# dual_power_supply.net
KiCad netlist of a schematic drawn in EAGLE
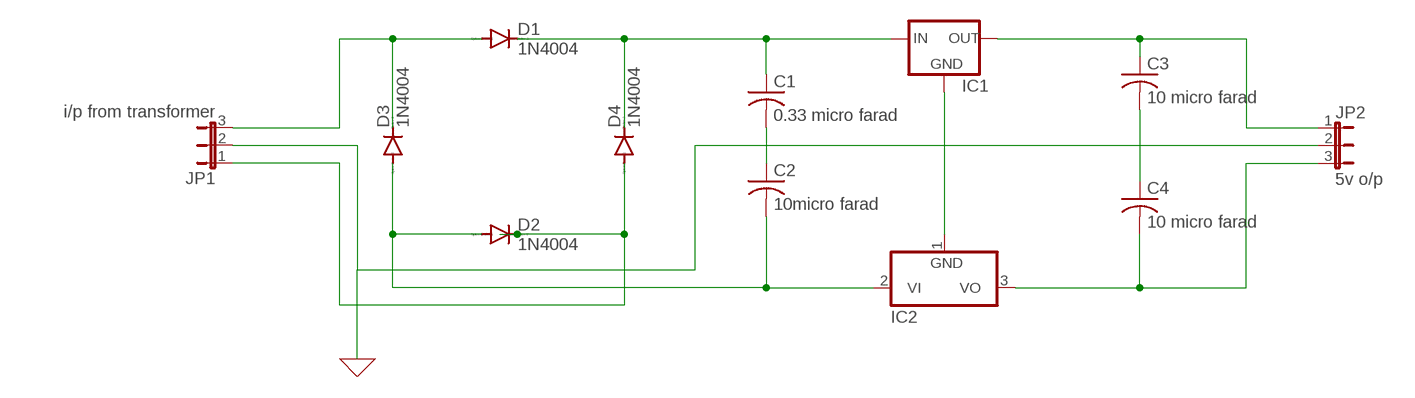
[diagram p0: schematic, sheet 1]

(export (version "E")
  (design (tool "Eeschema 10.0.6"))
  (components
    (comp (ref "C1")
      (value "0.33 micro farad")
      (footprint "eagle-import:C025-025X050")
      (libsource (lib "eagle-import") (part "C-US025-025X050"))
    )
    (comp (ref "C2")
      (value "10micro farad")
      (footprint "eagle-import:C025-025X050")
      (libsource (lib "eagle-import") (part "C-US025-025X050"))
    )
    (comp (ref "C3")
      (value "10 micro farad")
      (footprint "eagle-import:C025-025X050")
      (libsource (lib "eagle-import") (part "C-US025-025X050"))
    )
    (comp (ref "C4")
      (value "10 micro farad")
      (footprint "eagle-import:C025-025X050")
      (libsource (lib "eagle-import") (part "C-US025-025X050"))
    )
    (comp (ref "D1")
      (value "1N4004")
      (footprint "eagle-import:DO41-10")
      (libsource (lib "eagle-import") (part "1N4004"))
    )
    (comp (ref "D2")
      (value "1N4004")
      (footprint "eagle-import:DO41-10")
      (libsource (lib "eagle-import") (part "1N4004"))
    )
    (comp (ref "D3")
      (value "1N4004")
      (footprint "eagle-import:DO41-10")
      (libsource (lib "eagle-import") (part "1N4004"))
    )
    (comp (ref "D4")
      (value "1N4004")
      (footprint "eagle-import:DO41-10")
      (libsource (lib "eagle-import") (part "1N4004"))
    )
    (comp (ref "IC1")
      (value "78MXXS")
      (footprint "eagle-import:78MXXS")
      (libsource (lib "eagle-import") (part "78MXXS"))
    )
    (comp (ref "IC2")
      (value "7905L")
      (footprint "eagle-import:TO92")
      (libsource (lib "eagle-import") (part "79L05"))
    )
    (comp (ref "JP1")
      (value "i/p from transformer")
      (footprint "eagle-import:JP2")
      (libsource (lib "eagle-import") (part "JP2E"))
    )
    (comp (ref "JP2")
      (value "5v o/p")
      (footprint "eagle-import:JP2")
      (libsource (lib "eagle-import") (part "JP2E"))
    )
  )
  (nets
    (net (code "1") (name "GND") (class "Default")
      (node (ref "JP1") (pin "2") (pinfunction "2_2") (pintype "passive"))
      (node (ref "JP2") (pin "2") (pinfunction "2_2") (pintype "passive"))
    )
    (net (code "2") (name "Net-(C1-Pad1)") (class "Default")
      (node (ref "C1") (pin "1") (pinfunction "1_1") (pintype "passive"))
      (node (ref "D1") (pin "C") (pinfunction "C_C") (pintype "passive"))
      (node (ref "D4") (pin "C") (pinfunction "C_C") (pintype "passive"))
      (node (ref "IC1") (pin "IN") (pinfunction "IN_IN") (pintype "input"))
    )
    (net (code "3") (name "Net-(C1-Pad2)") (class "Default")
      (node (ref "C1") (pin "2") (pinfunction "2_2") (pintype "passive"))
      (node (ref "C2") (pin "1") (pinfunction "1_1") (pintype "passive"))
    )
    (net (code "4") (name "Net-(C3-Pad1)") (class "Default")
      (node (ref "C3") (pin "1") (pinfunction "1_1") (pintype "passive"))
      (node (ref "IC1") (pin "OUT") (pinfunction "OUT_OUT") (pintype "passive"))
      (node (ref "JP2") (pin "1") (pinfunction "1_1") (pintype "passive"))
    )
    (net (code "5") (name "Net-(C3-Pad2)") (class "Default")
      (node (ref "C3") (pin "2") (pinfunction "2_2") (pintype "passive"))
      (node (ref "C4") (pin "1") (pinfunction "1_1") (pintype "passive"))
    )
    (net (code "6") (name "Net-(D1-PadA)") (class "Default")
      (node (ref "D1") (pin "A") (pinfunction "A_A") (pintype "passive"))
      (node (ref "D3") (pin "C") (pinfunction "C_C") (pintype "passive"))
      (node (ref "JP1") (pin "3") (pinfunction "3_3") (pintype "passive"))
    )
    (net (code "7") (name "Net-(D2-PadC)") (class "Default")
      (node (ref "D2") (pin "C") (pinfunction "C_C") (pintype "passive"))
      (node (ref "D4") (pin "A") (pinfunction "A_A") (pintype "passive"))
      (node (ref "JP1") (pin "1") (pinfunction "1_1") (pintype "passive"))
    )
    (net (code "8") (name "Net-(IC2-GND)") (class "Default")
      (node (ref "IC1") (pin "GND") (pinfunction "GND_GND") (pintype "input"))
      (node (ref "IC2") (pin "1") (pinfunction "GND_1") (pintype "passive"))
    )
    (net (code "9") (name "Net-(IC2-VI)") (class "Default")
      (node (ref "C2") (pin "2") (pinfunction "2_2") (pintype "passive"))
      (node (ref "D2") (pin "A") (pinfunction "A_A") (pintype "passive"))
      (node (ref "D3") (pin "A") (pinfunction "A_A") (pintype "passive"))
      (node (ref "IC2") (pin "2") (pinfunction "VI_2") (pintype "input"))
    )
    (net (code "10") (name "Net-(IC2-VO)") (class "Default")
      (node (ref "C4") (pin "2") (pinfunction "2_2") (pintype "passive"))
      (node (ref "IC2") (pin "3") (pinfunction "VO_3") (pintype "passive"))
      (node (ref "JP2") (pin "3") (pinfunction "3_3") (pintype "passive"))
    )
  )
)
